# mainboard.net
KiCad netlist of a schematic drawn in EAGLE
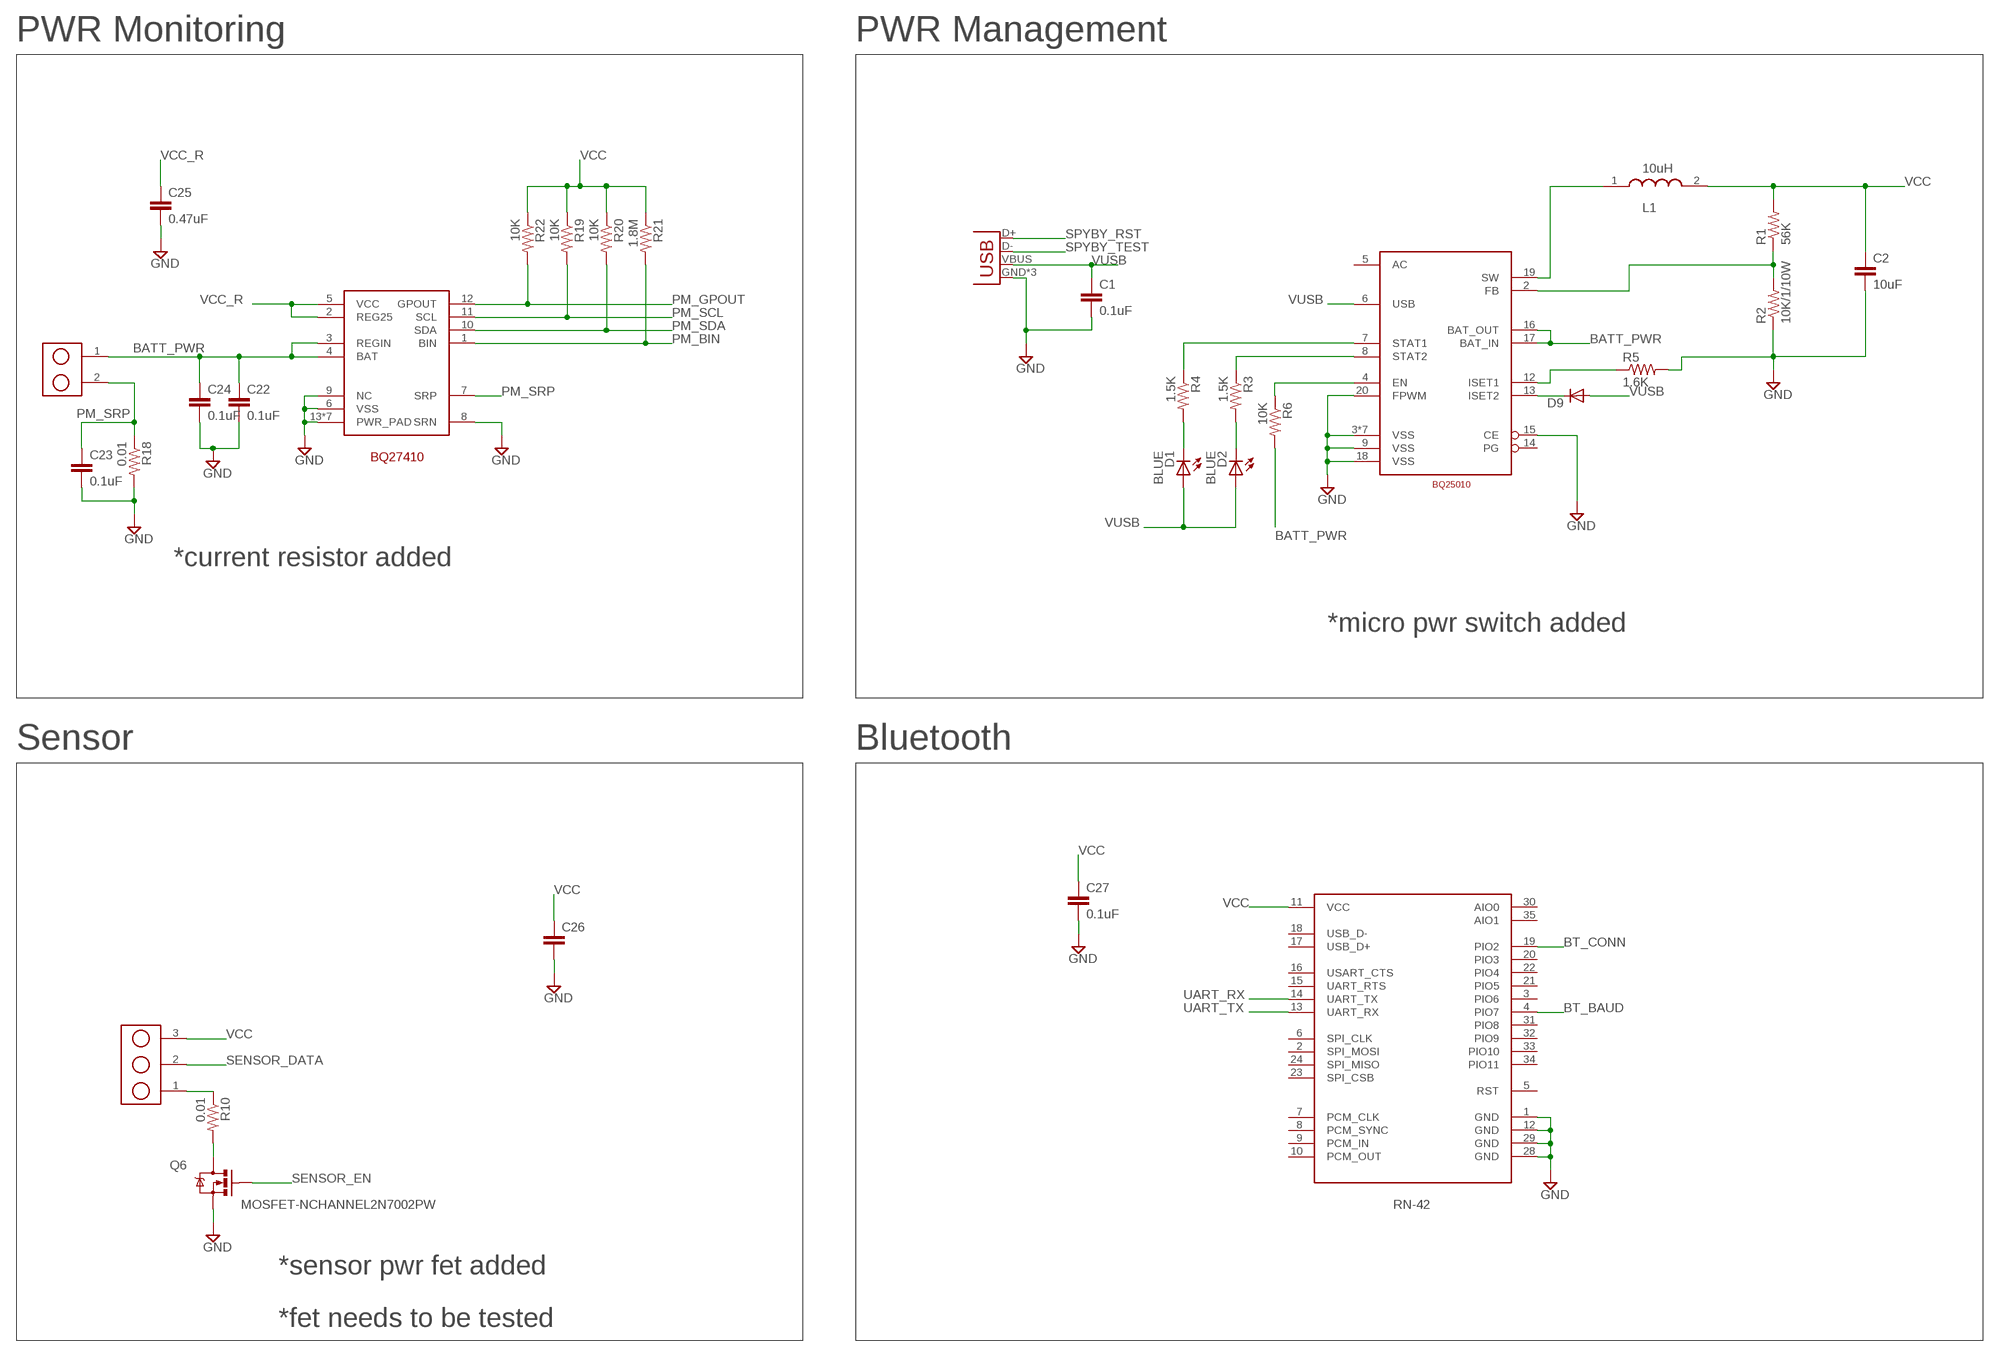
[diagram p0: schematic, sheet 1, part 1 of 2]
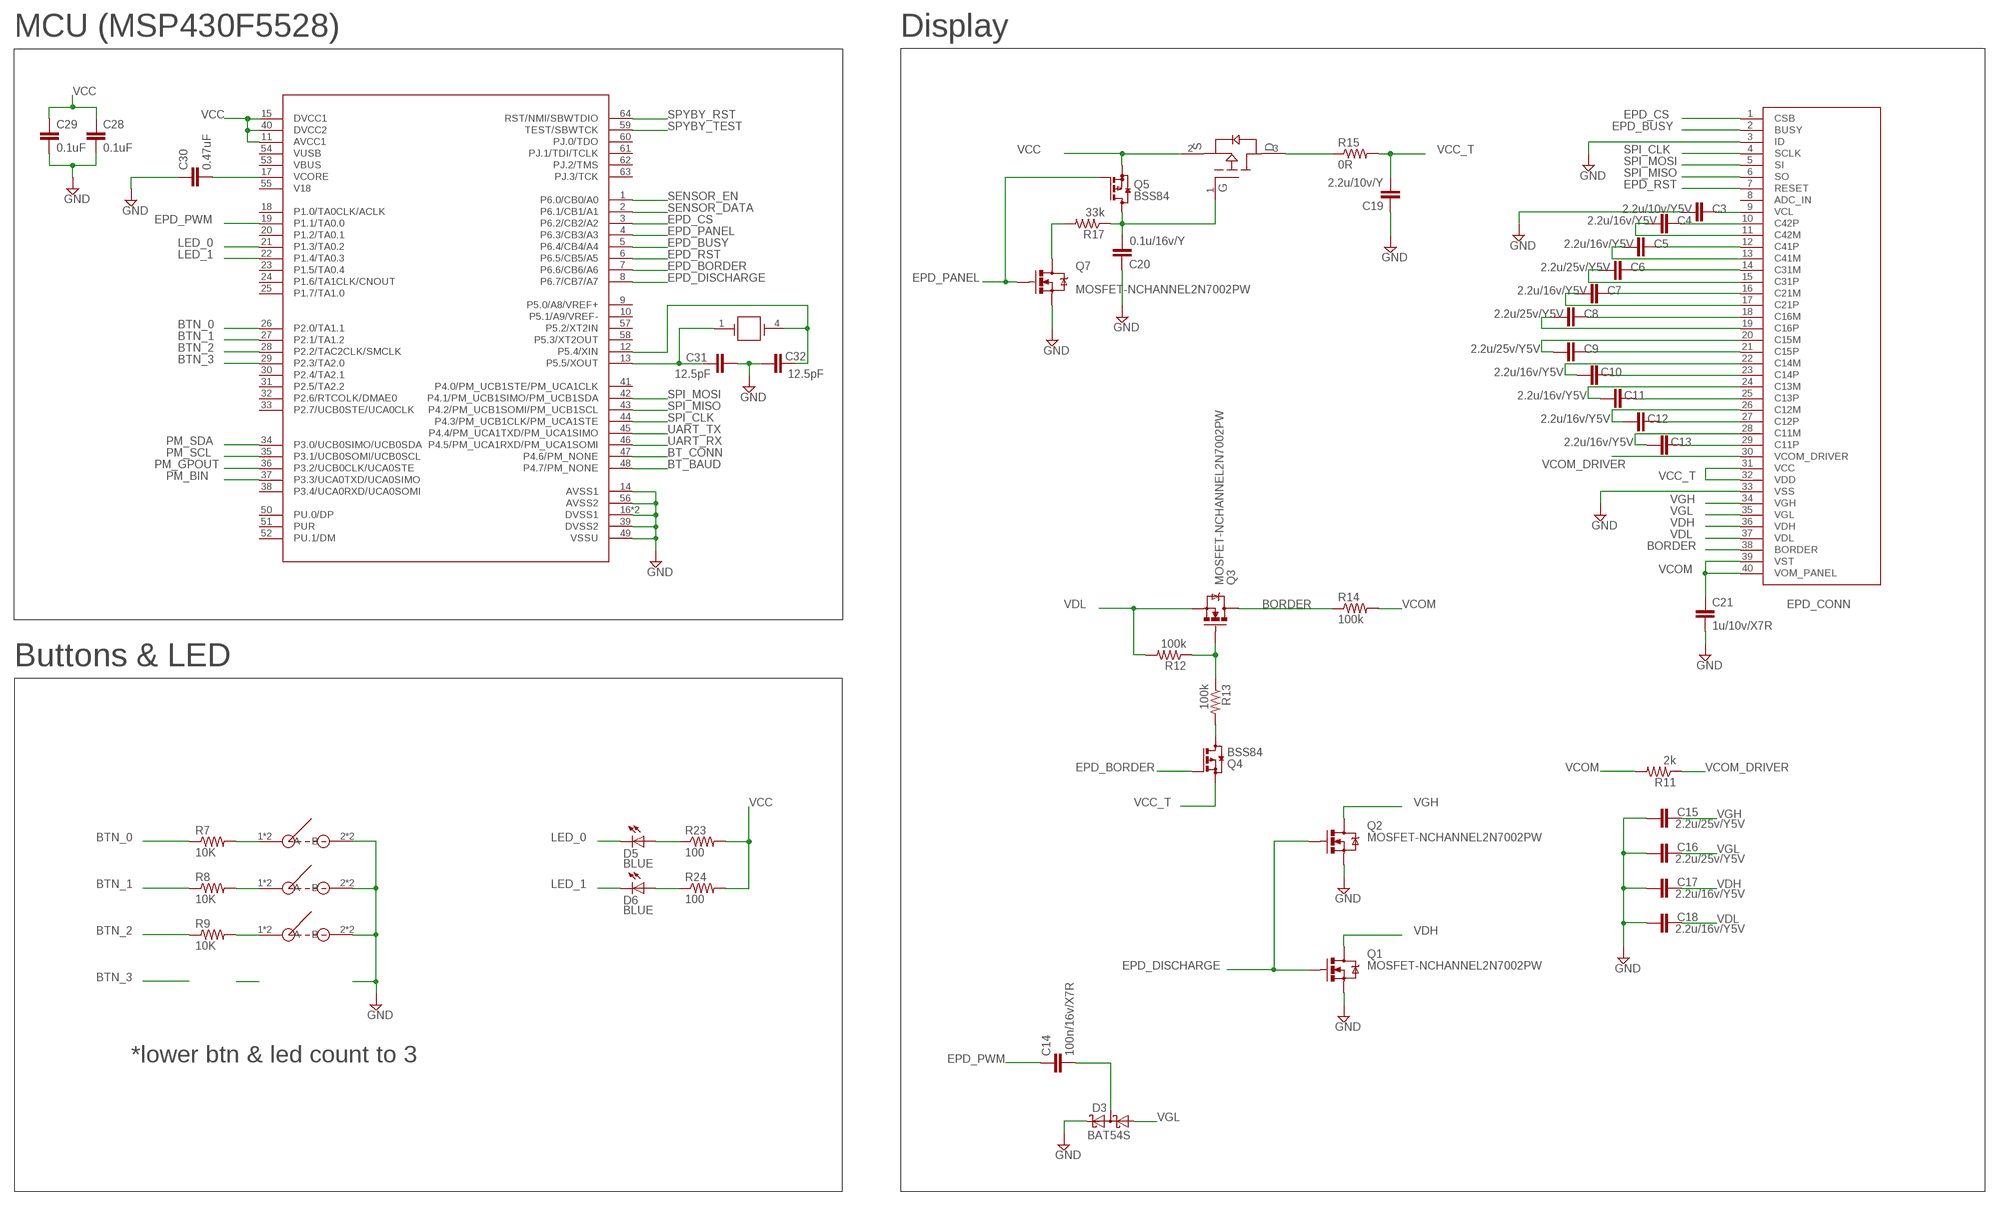
[diagram p1: schematic, sheet 1, part 2 of 2]

(export (version "E")
  (design (tool "Eeschema 10.0.6"))
  (components
    (comp (ref "AP2305")
      (value "DMG2305UX")
      (footprint "eagle-import:SOT23")
      (libsource (lib "eagle-import") (part "DMG2305UX"))
    )
    (comp (ref "C1")
      (value "0.1uF")
      (footprint "eagle-import:0402-CAP")
      (libsource (lib "eagle-import") (part "CAP0402-CAP"))
    )
    (comp (ref "C2")
      (value "10uF")
      (footprint "eagle-import:0402-CAP")
      (libsource (lib "eagle-import") (part "CAP0402-CAP"))
    )
    (comp (ref "C3")
      (value "2.2u/10v/Y5V")
      (footprint "eagle-import:0402-CAP")
      (libsource (lib "eagle-import") (part "CAP0402-CAP"))
    )
    (comp (ref "C4")
      (value "2.2u/16v/Y5V")
      (footprint "eagle-import:0402-CAP")
      (libsource (lib "eagle-import") (part "CAP0402-CAP"))
    )
    (comp (ref "C5")
      (value "2.2u/16v/Y5V")
      (footprint "eagle-import:0402-CAP")
      (libsource (lib "eagle-import") (part "CAP0402-CAP"))
    )
    (comp (ref "C6")
      (value "2.2u/25v/Y5V")
      (footprint "eagle-import:0402-CAP")
      (libsource (lib "eagle-import") (part "CAP0402-CAP"))
    )
    (comp (ref "C7")
      (value "2.2u/16v/Y5V")
      (footprint "eagle-import:0402-CAP")
      (libsource (lib "eagle-import") (part "CAP0402-CAP"))
    )
    (comp (ref "C8")
      (value "2.2u/25v/Y5V")
      (footprint "eagle-import:0402-CAP")
      (libsource (lib "eagle-import") (part "CAP0402-CAP"))
    )
    (comp (ref "C9")
      (value "2.2u/25v/Y5V")
      (footprint "eagle-import:0402-CAP")
      (libsource (lib "eagle-import") (part "CAP0402-CAP"))
    )
    (comp (ref "C10")
      (value "2.2u/16v/Y5V")
      (footprint "eagle-import:0402-CAP")
      (libsource (lib "eagle-import") (part "CAP0402-CAP"))
    )
    (comp (ref "C11")
      (value "2.2u/16v/Y5V")
      (footprint "eagle-import:0402-CAP")
      (libsource (lib "eagle-import") (part "CAP0402-CAP"))
    )
    (comp (ref "C12")
      (value "2.2u/16v/Y5V")
      (footprint "eagle-import:0402-CAP")
      (libsource (lib "eagle-import") (part "CAP0402-CAP"))
    )
    (comp (ref "C13")
      (value "2.2u/16v/Y5V")
      (footprint "eagle-import:0402-CAP")
      (libsource (lib "eagle-import") (part "CAP0402-CAP"))
    )
    (comp (ref "C14")
      (value "100n/16v/X7R")
      (footprint "eagle-import:0402-CAP")
      (libsource (lib "eagle-import") (part "CAP0402-CAP"))
    )
    (comp (ref "C15")
      (value "2.2u/25v/Y5V")
      (footprint "eagle-import:0402-CAP")
      (libsource (lib "eagle-import") (part "CAP0402-CAP"))
    )
    (comp (ref "C16")
      (value "2.2u/25v/Y5V")
      (footprint "eagle-import:0402-CAP")
      (libsource (lib "eagle-import") (part "CAP0402-CAP"))
    )
    (comp (ref "C17")
      (value "2.2u/16v/Y5V")
      (footprint "eagle-import:0402-CAP")
      (libsource (lib "eagle-import") (part "CAP0402-CAP"))
    )
    (comp (ref "C18")
      (value "2.2u/16v/Y5V")
      (footprint "eagle-import:0402-CAP")
      (libsource (lib "eagle-import") (part "CAP0402-CAP"))
    )
    (comp (ref "C19")
      (value "2.2u/10v/Y")
      (footprint "eagle-import:0402-CAP")
      (libsource (lib "eagle-import") (part "CAP0402-CAP"))
    )
    (comp (ref "C20")
      (value "0.1u/16v/Y")
      (footprint "eagle-import:0402-CAP")
      (libsource (lib "eagle-import") (part "CAP0402-CAP"))
    )
    (comp (ref "C21")
      (value "1u/10v/X7R")
      (footprint "eagle-import:0402-CAP")
      (libsource (lib "eagle-import") (part "CAP0402-CAP"))
    )
    (comp (ref "C22")
      (value "0.1uF")
      (footprint "eagle-import:0402-CAP")
      (libsource (lib "eagle-import") (part "CAP0402-CAP"))
    )
    (comp (ref "C23")
      (value "0.1uF")
      (footprint "eagle-import:0402-CAP")
      (libsource (lib "eagle-import") (part "CAP0402-CAP"))
    )
    (comp (ref "C24")
      (value "0.1uF")
      (footprint "eagle-import:0402-CAP")
      (libsource (lib "eagle-import") (part "CAP0402-CAP"))
    )
    (comp (ref "C25")
      (value "0.47uF")
      (footprint "eagle-import:0402-CAP")
      (libsource (lib "eagle-import") (part "CAP0402-CAP"))
    )
    (comp (ref "C26")
      (value "CAP0402-CAP")
      (footprint "eagle-import:0402-CAP")
      (libsource (lib "eagle-import") (part "CAP0402-CAP"))
    )
    (comp (ref "C27")
      (value "0.1uF")
      (footprint "eagle-import:0402-CAP")
      (libsource (lib "eagle-import") (part "CAP0402-CAP"))
    )
    (comp (ref "C28")
      (value "0.1uF")
      (footprint "eagle-import:0402-CAP")
      (libsource (lib "eagle-import") (part "CAP0402-CAP"))
    )
    (comp (ref "C29")
      (value "0.1uF")
      (footprint "eagle-import:0402-CAP")
      (libsource (lib "eagle-import") (part "CAP0402-CAP"))
    )
    (comp (ref "C30")
      (value "0.47uF")
      (footprint "eagle-import:0402-CAP")
      (libsource (lib "eagle-import") (part "CAP0402-CAP"))
    )
    (comp (ref "C31")
      (value "12.5pF")
      (footprint "eagle-import:0402-CAP")
      (libsource (lib "eagle-import") (part "CAP0402-CAP"))
    )
    (comp (ref "C32")
      (value "12.5pF")
      (footprint "eagle-import:0402-CAP")
      (libsource (lib "eagle-import") (part "CAP0402-CAP"))
    )
    (comp (ref "D1")
      (value "BLUE")
      (footprint "eagle-import:LED-0603")
      (libsource (lib "eagle-import") (part "LED-BLUE0603"))
    )
    (comp (ref "D2")
      (value "BLUE")
      (footprint "eagle-import:LED-0603")
      (libsource (lib "eagle-import") (part "LED-BLUE0603"))
    )
    (comp (ref "D3")
      (value "BAT54S")
      (footprint "eagle-import:SOT23")
      (libsource (lib "eagle-import") (part "BAT54S"))
    )
    (comp (ref "D5")
      (value "BLUE")
      (footprint "eagle-import:LED-0603")
      (libsource (lib "eagle-import") (part "LED-BLUE0603"))
    )
    (comp (ref "D6")
      (value "BLUE")
      (footprint "eagle-import:LED-0603")
      (libsource (lib "eagle-import") (part "LED-BLUE0603"))
    )
    (comp (ref "D9")
      (value "DIODESOD523")
      (footprint "eagle-import:SOD523")
      (libsource (lib "eagle-import") (part "DIODESOD523"))
    )
    (comp (ref "JP1")
      (value "USB-MICROB")
      (footprint "eagle-import:USB-MICROB")
      (libsource (lib "eagle-import") (part "USB-MICROB"))
    )
    (comp (ref "L1")
      (value "10uH")
      (footprint "eagle-import:ASPI_0428S-100M-T")
      (libsource (lib "eagle-import") (part "ASPI-0428S-100M-T"))
    )
    (comp (ref "Q1")
      (value "MOSFET-NCHANNEL2N7002PW")
      (footprint "eagle-import:SOT323")
      (libsource (lib "eagle-import") (part "MOSFET-NCHANNEL2N7002PW"))
    )
    (comp (ref "Q2")
      (value "MOSFET-NCHANNEL2N7002PW")
      (footprint "eagle-import:SOT323")
      (libsource (lib "eagle-import") (part "MOSFET-NCHANNEL2N7002PW"))
    )
    (comp (ref "Q3")
      (value "MOSFET-NCHANNEL2N7002PW")
      (footprint "eagle-import:SOT323")
      (libsource (lib "eagle-import") (part "MOSFET-NCHANNEL2N7002PW"))
    )
    (comp (ref "Q4")
      (value "BSS84")
      (footprint "eagle-import:SOT23")
      (libsource (lib "eagle-import") (part "BSS84"))
    )
    (comp (ref "Q5")
      (value "BSS84")
      (footprint "eagle-import:SOT23")
      (libsource (lib "eagle-import") (part "BSS84"))
    )
    (comp (ref "Q6")
      (value "MOSFET-NCHANNEL2N7002PW")
      (footprint "eagle-import:SOT323")
      (libsource (lib "eagle-import") (part "MOSFET-NCHANNEL2N7002PW"))
    )
    (comp (ref "Q7")
      (value "MOSFET-NCHANNEL2N7002PW")
      (footprint "eagle-import:SOT323")
      (libsource (lib "eagle-import") (part "MOSFET-NCHANNEL2N7002PW"))
    )
    (comp (ref "R1")
      (value "56K")
      (footprint "eagle-import:0402-RES")
      (libsource (lib "eagle-import") (part "RESISTOR0402-RES"))
    )
    (comp (ref "R2")
      (value "10K/1/10W")
      (footprint "eagle-import:0402-RES")
      (libsource (lib "eagle-import") (part "RESISTOR0402-RES"))
    )
    (comp (ref "R3")
      (value "1.5K")
      (footprint "eagle-import:0402-RES")
      (libsource (lib "eagle-import") (part "RESISTOR0402-RES"))
    )
    (comp (ref "R4")
      (value "1.5K")
      (footprint "eagle-import:0402-RES")
      (libsource (lib "eagle-import") (part "RESISTOR0402-RES"))
    )
    (comp (ref "R5")
      (value "1.6K")
      (footprint "eagle-import:0402-RES")
      (libsource (lib "eagle-import") (part "RESISTOR0402-RES"))
    )
    (comp (ref "R6")
      (value "10K")
      (footprint "eagle-import:0402-RES")
      (libsource (lib "eagle-import") (part "RESISTOR0402-RES"))
    )
    (comp (ref "R7")
      (value "10K")
      (footprint "eagle-import:0402-RES")
      (libsource (lib "eagle-import") (part "RESISTOR0402-RES"))
    )
    (comp (ref "R8")
      (value "10K")
      (footprint "eagle-import:0402-RES")
      (libsource (lib "eagle-import") (part "RESISTOR0402-RES"))
    )
    (comp (ref "R9")
      (value "10K")
      (footprint "eagle-import:0402-RES")
      (libsource (lib "eagle-import") (part "RESISTOR0402-RES"))
    )
    (comp (ref "R10")
      (value "0.01")
      (footprint "eagle-import:0402-RES")
      (libsource (lib "eagle-import") (part "RESISTOR0402-RES"))
    )
    (comp (ref "R11")
      (value "2k")
      (footprint "eagle-import:0402-RES")
      (libsource (lib "eagle-import") (part "RESISTOR0402-RES"))
    )
    (comp (ref "R12")
      (value "100k")
      (footprint "eagle-import:0402-RES")
      (libsource (lib "eagle-import") (part "RESISTOR0402-RES"))
    )
    (comp (ref "R13")
      (value "100k")
      (footprint "eagle-import:0402-RES")
      (libsource (lib "eagle-import") (part "RESISTOR0402-RES"))
    )
    (comp (ref "R14")
      (value "100k")
      (footprint "eagle-import:0402-RES")
      (libsource (lib "eagle-import") (part "RESISTOR0402-RES"))
    )
    (comp (ref "R15")
      (value "0R")
      (footprint "eagle-import:0402-RES")
      (libsource (lib "eagle-import") (part "RESISTOR0402-RES"))
    )
    (comp (ref "R17")
      (value "33k")
      (footprint "eagle-import:0402-RES")
      (libsource (lib "eagle-import") (part "RESISTOR0402-RES"))
    )
    (comp (ref "R18")
      (value "0.01")
      (footprint "eagle-import:0402-RES")
      (libsource (lib "eagle-import") (part "RESISTOR0402-RES"))
    )
    (comp (ref "R19")
      (value "10K")
      (footprint "eagle-import:0402-RES")
      (libsource (lib "eagle-import") (part "RESISTOR0402-RES"))
    )
    (comp (ref "R20")
      (value "10K")
      (footprint "eagle-import:0402-RES")
      (libsource (lib "eagle-import") (part "RESISTOR0402-RES"))
    )
    (comp (ref "R21")
      (value "1.8M")
      (footprint "eagle-import:0402-RES")
      (libsource (lib "eagle-import") (part "RESISTOR0402-RES"))
    )
    (comp (ref "R22")
      (value "10K")
      (footprint "eagle-import:0402-RES")
      (libsource (lib "eagle-import") (part "RESISTOR0402-RES"))
    )
    (comp (ref "R23")
      (value "100")
      (footprint "eagle-import:0402-RES")
      (libsource (lib "eagle-import") (part "RESISTOR0402-RES"))
    )
    (comp (ref "R24")
      (value "100")
      (footprint "eagle-import:0402-RES")
      (libsource (lib "eagle-import") (part "RESISTOR0402-RES"))
    )
    (comp (ref "U$1")
      (value "MSP430F5528")
      (footprint "eagle-import:VQFN_RGC_64PIN")
      (libsource (lib "eagle-import") (part "MSP430F5528"))
    )
    (comp (ref "U$2")
      (value "RN-42")
      (footprint "eagle-import:RN-42")
      (libsource (lib "eagle-import") (part "RN-42"))
    )
    (comp (ref "U$3")
      (value "BQ25010")
      (footprint "eagle-import:VQFN_RHL_20PIN")
      (libsource (lib "eagle-import") (part "BQ25010"))
    )
    (comp (ref "U$4")
      (value "RA_TAC_BUTTON\"EVQPUK\"")
      (footprint "eagle-import:EVQ-PUK02K")
      (fields (field (name "PART#") "EVQ-PUK02K"))
      (libsource (lib "eagle-import") (part "RA_TAC_BUTTON{dblquote}EVQPUK{dblquote}"))
    )
    (comp (ref "U$5")
      (value "RA_TAC_BUTTON\"EVQPUK\"")
      (footprint "eagle-import:EVQ-PUK02K")
      (fields (field (name "PART#") "EVQ-PUK02K"))
      (libsource (lib "eagle-import") (part "RA_TAC_BUTTON{dblquote}EVQPUK{dblquote}"))
    )
    (comp (ref "U$6")
      (value "RA_TAC_BUTTON\"EVQPUK\"")
      (footprint "eagle-import:EVQ-PUK02K")
      (fields (field (name "PART#") "EVQ-PUK02K"))
      (libsource (lib "eagle-import") (part "RA_TAC_BUTTON{dblquote}EVQPUK{dblquote}"))
    )
    (comp (ref "U$8")
      (value "FH12-40S-0.5SH")
      (footprint "eagle-import:FH12-40S-0.5SH")
      (libsource (lib "eagle-import") (part "FH12-40S-0.5SH"))
    )
    (comp (ref "U$9")
      (value "BQ27410")
      (footprint "eagle-import:SON_DRZ_12PIN")
      (libsource (lib "eagle-import") (part "BQ27410"))
    )
    (comp (ref "U$11")
      (value "HEADER_2PIN_50MIL")
      (footprint "eagle-import:HEADER_2PIN_50MIL")
      (libsource (lib "eagle-import") (part "HEADER_2PIN_50MIL"))
    )
    (comp (ref "U$12")
      (value "HEADER_3PIN_50MIL")
      (footprint "eagle-import:HEADER_3PIN_50MIL")
      (libsource (lib "eagle-import") (part "HEADER_3PIN_50MIL"))
    )
    (comp (ref "X1")
      (value "CRYSTAL\"32.768\"")
      (footprint "eagle-import:ECS-327-12.5-17X-C-TR")
      (libsource (lib "eagle-import") (part "CRYSTAL{dblquote}32.768{dblquote}"))
    )
  )
  (nets
    (net (code "1") (name "/BATT_PWR") (class "Default")
      (node (ref "C22") (pin "1") (pinfunction "1_1") (pintype "passive"))
      (node (ref "C24") (pin "1") (pinfunction "1_1") (pintype "passive"))
      (node (ref "R6") (pin "2") (pinfunction "2_2") (pintype "passive"))
      (node (ref "U$11") (pin "1") (pinfunction "1_1") (pintype "bidirectional"))
      (node (ref "U$3") (pin "16") (pinfunction "BAT_OUT_16") (pintype "bidirectional"))
      (node (ref "U$3") (pin "17") (pinfunction "BAT_IN_17") (pintype "bidirectional"))
      (node (ref "U$9") (pin "3") (pinfunction "REGIN_3") (pintype "bidirectional"))
      (node (ref "U$9") (pin "4") (pinfunction "BAT_4") (pintype "bidirectional"))
    )
    (net (code "2") (name "/BORDER") (class "Default")
      (node (ref "Q3") (pin "3") (pinfunction "D_3") (pintype "passive"))
      (node (ref "R14") (pin "1") (pinfunction "1_1") (pintype "passive"))
      (node (ref "U$8") (pin "38") (pinfunction "BORDER_38") (pintype "bidirectional"))
    )
    (net (code "3") (name "/BTN_0") (class "Default")
      (node (ref "R7") (pin "1") (pinfunction "1_1") (pintype "passive"))
      (node (ref "U$1") (pin "26") (pinfunction "P2.0/TA1.1_26") (pintype "bidirectional"))
    )
    (net (code "4") (name "/BTN_1") (class "Default")
      (node (ref "R8") (pin "1") (pinfunction "1_1") (pintype "passive"))
      (node (ref "U$1") (pin "27") (pinfunction "P2.1/TA1.2_27") (pintype "bidirectional"))
    )
    (net (code "5") (name "/BTN_2") (class "Default")
      (node (ref "R9") (pin "1") (pinfunction "1_1") (pintype "passive"))
      (node (ref "U$1") (pin "28") (pinfunction "P2.2/TAC2CLK/SMCLK_28") (pintype "bidirectional"))
    )
    (net (code "6") (name "/BTN_3") (class "Default")
      (node (ref "U$1") (pin "29") (pinfunction "P2.3/TA2.0_29") (pintype "bidirectional"))
    )
    (net (code "7") (name "/BT_BAUD") (class "Default")
      (node (ref "U$1") (pin "48") (pinfunction "P4.7/PM_NONE_48") (pintype "bidirectional"))
      (node (ref "U$2") (pin "4") (pinfunction "PIO7_4") (pintype "bidirectional"))
    )
    (net (code "8") (name "/BT_CONN") (class "Default")
      (node (ref "U$1") (pin "47") (pinfunction "P4.6/PM_NONE_47") (pintype "bidirectional"))
      (node (ref "U$2") (pin "19") (pinfunction "PIO2_19") (pintype "bidirectional"))
    )
    (net (code "9") (name "/EPD_BORDER") (class "Default")
      (node (ref "Q4") (pin "1") (pinfunction "G_1") (pintype "passive"))
      (node (ref "U$1") (pin "7") (pinfunction "P6.6/CB6/A6_7") (pintype "bidirectional"))
    )
    (net (code "10") (name "/EPD_BUSY") (class "Default")
      (node (ref "U$1") (pin "5") (pinfunction "P6.4/CB4/A4_5") (pintype "bidirectional"))
      (node (ref "U$8") (pin "2") (pinfunction "BUSY_2") (pintype "bidirectional"))
    )
    (net (code "11") (name "/EPD_CS") (class "Default")
      (node (ref "U$1") (pin "3") (pinfunction "P6.2/CB2/A2_3") (pintype "bidirectional"))
      (node (ref "U$8") (pin "1") (pinfunction "CSB_1") (pintype "bidirectional"))
    )
    (net (code "12") (name "/EPD_DISCHARGE") (class "Default")
      (node (ref "Q1") (pin "1") (pinfunction "G_1") (pintype "passive"))
      (node (ref "Q2") (pin "1") (pinfunction "G_1") (pintype "passive"))
      (node (ref "U$1") (pin "8") (pinfunction "P6.7/CB7/A7_8") (pintype "bidirectional"))
    )
    (net (code "13") (name "/EPD_PANEL") (class "Default")
      (node (ref "Q5") (pin "1") (pinfunction "G_1") (pintype "passive"))
      (node (ref "Q7") (pin "1") (pinfunction "G_1") (pintype "passive"))
      (node (ref "U$1") (pin "4") (pinfunction "P6.3/CB3/A3_4") (pintype "bidirectional"))
    )
    (net (code "14") (name "/EPD_PWM") (class "Default")
      (node (ref "C14") (pin "1") (pinfunction "1_1") (pintype "passive"))
      (node (ref "U$1") (pin "19") (pinfunction "P1.1/TA0.0_19") (pintype "bidirectional"))
    )
    (net (code "15") (name "/EPD_RST") (class "Default")
      (node (ref "U$1") (pin "6") (pinfunction "P6.5/CB5/A5_6") (pintype "bidirectional"))
      (node (ref "U$8") (pin "7") (pinfunction "RESET_7") (pintype "bidirectional"))
    )
    (net (code "16") (name "/LED_0") (class "Default")
      (node (ref "D5") (pin "C") (pinfunction "C_C") (pintype "passive"))
      (node (ref "U$1") (pin "21") (pinfunction "P1.3/TA0.2_21") (pintype "bidirectional"))
    )
    (net (code "17") (name "/LED_1") (class "Default")
      (node (ref "D6") (pin "C") (pinfunction "C_C") (pintype "passive"))
      (node (ref "U$1") (pin "22") (pinfunction "P1.4/TA0.3_22") (pintype "bidirectional"))
    )
    (net (code "18") (name "/PM_BIN") (class "Default")
      (node (ref "R21") (pin "2") (pinfunction "2_2") (pintype "passive"))
      (node (ref "U$1") (pin "37") (pinfunction "P3.3/UCA0TXD/UCA0SIMO_37") (pintype "bidirectional"))
      (node (ref "U$9") (pin "1") (pinfunction "BIN_1") (pintype "bidirectional"))
    )
    (net (code "19") (name "/PM_GPOUT") (class "Default")
      (node (ref "R22") (pin "2") (pinfunction "2_2") (pintype "passive"))
      (node (ref "U$1") (pin "36") (pinfunction "P3.2/UCB0CLK/UCA0STE_36") (pintype "bidirectional"))
      (node (ref "U$9") (pin "12") (pinfunction "GPOUT_12") (pintype "bidirectional"))
    )
    (net (code "20") (name "/PM_SCL") (class "Default")
      (node (ref "R19") (pin "2") (pinfunction "2_2") (pintype "passive"))
      (node (ref "U$1") (pin "35") (pinfunction "P3.1/UCB0SOMI/UCB0SCL_35") (pintype "bidirectional"))
      (node (ref "U$9") (pin "11") (pinfunction "SCL_11") (pintype "bidirectional"))
    )
    (net (code "21") (name "/PM_SDA") (class "Default")
      (node (ref "R20") (pin "2") (pinfunction "2_2") (pintype "passive"))
      (node (ref "U$1") (pin "34") (pinfunction "P3.0/UCB0SIMO/UCB0SDA_34") (pintype "bidirectional"))
      (node (ref "U$9") (pin "10") (pinfunction "SDA_10") (pintype "bidirectional"))
    )
    (net (code "22") (name "/PM_SRP") (class "Default")
      (node (ref "C23") (pin "1") (pinfunction "1_1") (pintype "passive"))
      (node (ref "R18") (pin "1") (pinfunction "1_1") (pintype "passive"))
      (node (ref "U$11") (pin "2") (pinfunction "2_2") (pintype "bidirectional"))
      (node (ref "U$9") (pin "7") (pinfunction "SRP_7") (pintype "bidirectional"))
    )
    (net (code "23") (name "/SENSOR_DATA") (class "Default")
      (node (ref "U$1") (pin "2") (pinfunction "P6.1/CB1/A1_2") (pintype "bidirectional"))
      (node (ref "U$12") (pin "2") (pinfunction "P$2_2") (pintype "bidirectional"))
    )
    (net (code "24") (name "/SENSOR_EN") (class "Default")
      (node (ref "Q6") (pin "1") (pinfunction "G_1") (pintype "passive"))
      (node (ref "U$1") (pin "1") (pinfunction "P6.0/CB0/A0_1") (pintype "bidirectional"))
    )
    (net (code "25") (name "/SPI_CLK") (class "Default")
      (node (ref "U$1") (pin "44") (pinfunction "P4.3/PM_UCB1CLK/PM_UCA1STE_44") (pintype "bidirectional"))
      (node (ref "U$8") (pin "4") (pinfunction "SCLK_4") (pintype "bidirectional"))
    )
    (net (code "26") (name "/SPI_MISO") (class "Default")
      (node (ref "U$1") (pin "43") (pinfunction "P4.2/PM_UCB1SOMI/PM_UCB1SCL_43") (pintype "bidirectional"))
      (node (ref "U$8") (pin "6") (pinfunction "SO_6") (pintype "bidirectional"))
    )
    (net (code "27") (name "/SPI_MOSI") (class "Default")
      (node (ref "U$1") (pin "42") (pinfunction "P4.1/PM_UCB1SIMO/PM_UCB1SDA_42") (pintype "bidirectional"))
      (node (ref "U$8") (pin "5") (pinfunction "SI_5") (pintype "bidirectional"))
    )
    (net (code "28") (name "/SPYBY_RST") (class "Default")
      (node (ref "JP1") (pin "D+") (pinfunction "D+_D+") (pintype "bidirectional"))
      (node (ref "U$1") (pin "64") (pinfunction "RST/NMI/SBWTDIO_64") (pintype "bidirectional"))
    )
    (net (code "29") (name "/SPYBY_TEST") (class "Default")
      (node (ref "JP1") (pin "D-") (pinfunction "D-_D-") (pintype "bidirectional"))
      (node (ref "U$1") (pin "59") (pinfunction "TEST/SBWTCK_59") (pintype "bidirectional"))
    )
    (net (code "30") (name "/UART_RX") (class "Default")
      (node (ref "U$1") (pin "46") (pinfunction "P4.5/PM_UCA1RXD/PM_UCA1SOMI_46") (pintype "bidirectional"))
      (node (ref "U$2") (pin "14") (pinfunction "UART_TX_14") (pintype "bidirectional"))
    )
    (net (code "31") (name "/UART_TX") (class "Default")
      (node (ref "U$1") (pin "45") (pinfunction "P4.4/PM_UCA1TXD/PM_UCA1SIMO_45") (pintype "bidirectional"))
      (node (ref "U$2") (pin "13") (pinfunction "UART_RX_13") (pintype "bidirectional"))
    )
    (net (code "32") (name "/VCC") (class "Default")
      (node (ref "AP2305") (pin "2") (pinfunction "SOURCE_2") (pintype "bidirectional"))
      (node (ref "C2") (pin "1") (pinfunction "1_1") (pintype "passive"))
      (node (ref "C26") (pin "1") (pinfunction "1_1") (pintype "passive"))
      (node (ref "C27") (pin "1") (pinfunction "1_1") (pintype "passive"))
      (node (ref "C28") (pin "1") (pinfunction "1_1") (pintype "passive"))
      (node (ref "C29") (pin "1") (pinfunction "1_1") (pintype "passive"))
      (node (ref "L1") (pin "2") (pinfunction "P$2_2") (pintype "bidirectional"))
      (node (ref "Q5") (pin "2") (pinfunction "S_2") (pintype "passive"))
      (node (ref "R1") (pin "2") (pinfunction "2_2") (pintype "passive"))
      (node (ref "R19") (pin "1") (pinfunction "1_1") (pintype "passive"))
      (node (ref "R20") (pin "1") (pinfunction "1_1") (pintype "passive"))
      (node (ref "R21") (pin "1") (pinfunction "1_1") (pintype "passive"))
      (node (ref "R22") (pin "1") (pinfunction "1_1") (pintype "passive"))
      (node (ref "R23") (pin "2") (pinfunction "2_2") (pintype "passive"))
      (node (ref "R24") (pin "2") (pinfunction "2_2") (pintype "passive"))
      (node (ref "U$1") (pin "11") (pinfunction "AVCC1_11") (pintype "bidirectional"))
      (node (ref "U$1") (pin "15") (pinfunction "DVCC1_15") (pintype "bidirectional"))
      (node (ref "U$1") (pin "40") (pinfunction "DVCC2_40") (pintype "bidirectional"))
      (node (ref "U$12") (pin "3") (pinfunction "P$3_3") (pintype "bidirectional"))
      (node (ref "U$2") (pin "11") (pinfunction "VCC_11") (pintype "bidirectional"))
    )
    (net (code "33") (name "/VCC_R") (class "Default")
      (node (ref "C25") (pin "1") (pinfunction "1_1") (pintype "passive"))
      (node (ref "U$9") (pin "2") (pinfunction "REG25_2") (pintype "bidirectional"))
      (node (ref "U$9") (pin "5") (pinfunction "VCC_5") (pintype "bidirectional"))
    )
    (net (code "34") (name "/VCC_T") (class "Default")
      (node (ref "C19") (pin "2") (pinfunction "2_2") (pintype "passive"))
      (node (ref "Q4") (pin "2") (pinfunction "S_2") (pintype "passive"))
      (node (ref "R15") (pin "2") (pinfunction "2_2") (pintype "passive"))
      (node (ref "U$8") (pin "31") (pinfunction "VCC_31") (pintype "bidirectional"))
      (node (ref "U$8") (pin "32") (pinfunction "VDD_32") (pintype "bidirectional"))
    )
    (net (code "35") (name "/VCOM") (class "Default")
      (node (ref "C21") (pin "1") (pinfunction "1_1") (pintype "passive"))
      (node (ref "R11") (pin "2") (pinfunction "2_2") (pintype "passive"))
      (node (ref "R14") (pin "2") (pinfunction "2_2") (pintype "passive"))
      (node (ref "U$8") (pin "39") (pinfunction "VST_39") (pintype "bidirectional"))
      (node (ref "U$8") (pin "40") (pinfunction "VOM_PANEL_40") (pintype "bidirectional"))
    )
    (net (code "36") (name "/VCOM_DRIVER") (class "Default")
      (node (ref "R11") (pin "1") (pinfunction "1_1") (pintype "passive"))
      (node (ref "U$8") (pin "30") (pinfunction "VCOM_DRIVER_30") (pintype "bidirectional"))
    )
    (net (code "37") (name "/VDH") (class "Default")
      (node (ref "C17") (pin "2") (pinfunction "2_2") (pintype "passive"))
      (node (ref "Q1") (pin "3") (pinfunction "D_3") (pintype "passive"))
      (node (ref "U$8") (pin "36") (pinfunction "VDH_36") (pintype "bidirectional"))
    )
    (net (code "38") (name "/VDL") (class "Default")
      (node (ref "C18") (pin "2") (pinfunction "2_2") (pintype "passive"))
      (node (ref "Q3") (pin "2") (pinfunction "S_2") (pintype "passive"))
      (node (ref "R12") (pin "2") (pinfunction "2_2") (pintype "passive"))
      (node (ref "U$8") (pin "37") (pinfunction "VDL_37") (pintype "bidirectional"))
    )
    (net (code "39") (name "/VGH") (class "Default")
      (node (ref "C15") (pin "2") (pinfunction "2_2") (pintype "passive"))
      (node (ref "Q2") (pin "3") (pinfunction "D_3") (pintype "passive"))
      (node (ref "U$8") (pin "34") (pinfunction "VGH_34") (pintype "bidirectional"))
    )
    (net (code "40") (name "/VGL") (class "Default")
      (node (ref "C16") (pin "2") (pinfunction "2_2") (pintype "passive"))
      (node (ref "D3") (pin "1") (pinfunction "A1_1") (pintype "passive"))
      (node (ref "U$8") (pin "35") (pinfunction "VGL_35") (pintype "bidirectional"))
    )
    (net (code "41") (name "/VUSB") (class "Default")
      (node (ref "C1") (pin "1") (pinfunction "1_1") (pintype "passive"))
      (node (ref "D1") (pin "A") (pinfunction "A_A") (pintype "passive"))
      (node (ref "D2") (pin "A") (pinfunction "A_A") (pintype "passive"))
      (node (ref "D9") (pin "A") (pinfunction "A_A") (pintype "passive"))
      (node (ref "JP1") (pin "VBUS") (pinfunction "VBUS_VBUS") (pintype "bidirectional"))
      (node (ref "U$3") (pin "6") (pinfunction "USB_6") (pintype "bidirectional"))
    )
    (net (code "42") (name "GND") (class "Default")
      (node (ref "C1") (pin "2") (pinfunction "2_2") (pintype "passive"))
      (node (ref "C15") (pin "1") (pinfunction "1_1") (pintype "passive"))
      (node (ref "C16") (pin "1") (pinfunction "1_1") (pintype "passive"))
      (node (ref "C17") (pin "1") (pinfunction "1_1") (pintype "passive"))
      (node (ref "C18") (pin "1") (pinfunction "1_1") (pintype "passive"))
      (node (ref "C19") (pin "1") (pinfunction "1_1") (pintype "passive"))
      (node (ref "C2") (pin "2") (pinfunction "2_2") (pintype "passive"))
      (node (ref "C20") (pin "1") (pinfunction "1_1") (pintype "passive"))
      (node (ref "C21") (pin "2") (pinfunction "2_2") (pintype "passive"))
      (node (ref "C22") (pin "2") (pinfunction "2_2") (pintype "passive"))
      (node (ref "C23") (pin "2") (pinfunction "2_2") (pintype "passive"))
      (node (ref "C24") (pin "2") (pinfunction "2_2") (pintype "passive"))
      (node (ref "C25") (pin "2") (pinfunction "2_2") (pintype "passive"))
      (node (ref "C26") (pin "2") (pinfunction "2_2") (pintype "passive"))
      (node (ref "C27") (pin "2") (pinfunction "2_2") (pintype "passive"))
      (node (ref "C28") (pin "2") (pinfunction "2_2") (pintype "passive"))
      (node (ref "C29") (pin "2") (pinfunction "2_2") (pintype "passive"))
      (node (ref "C3") (pin "1") (pinfunction "1_1") (pintype "passive"))
      (node (ref "C30") (pin "1") (pinfunction "1_1") (pintype "passive"))
      (node (ref "C31") (pin "2") (pinfunction "2_2") (pintype "passive"))
      (node (ref "C32") (pin "1") (pinfunction "1_1") (pintype "passive"))
      (node (ref "D3") (pin "2") (pinfunction "C2_2") (pintype "passive"))
      (node (ref "JP1") (pin "GND") (pinfunction "GND_GND") (pintype "bidirectional"))
      (node (ref "JP1") (pin "MT1") (pinfunction "GND_MT1") (pintype "bidirectional"))
      (node (ref "JP1") (pin "MT2") (pinfunction "GND_MT2") (pintype "bidirectional"))
      (node (ref "Q1") (pin "2") (pinfunction "S_2") (pintype "passive"))
      (node (ref "Q2") (pin "2") (pinfunction "S_2") (pintype "passive"))
      (node (ref "Q6") (pin "2") (pinfunction "S_2") (pintype "passive"))
      (node (ref "Q7") (pin "2") (pinfunction "S_2") (pintype "passive"))
      (node (ref "R18") (pin "2") (pinfunction "2_2") (pintype "passive"))
      (node (ref "R2") (pin "1") (pinfunction "1_1") (pintype "passive"))
      (node (ref "R5") (pin "2") (pinfunction "2_2") (pintype "passive"))
      (node (ref "U$1") (pin "14") (pinfunction "AVSS1_14") (pintype "bidirectional"))
      (node (ref "U$1") (pin "16") (pinfunction "DVSS1_16") (pintype "bidirectional"))
      (node (ref "U$1") (pin "39") (pinfunction "DVSS2_39") (pintype "bidirectional"))
      (node (ref "U$1") (pin "49") (pinfunction "VSSU_49") (pintype "bidirectional"))
      (node (ref "U$1") (pin "56") (pinfunction "AVSS2_56") (pintype "bidirectional"))
      (node (ref "U$1") (pin "P$1") (pinfunction "DVSS1_P$1") (pintype "bidirectional"))
      (node (ref "U$2") (pin "1") (pinfunction "GND_1") (pintype "bidirectional"))
      (node (ref "U$2") (pin "12") (pinfunction "GND_12") (pintype "bidirectional"))
      (node (ref "U$2") (pin "28") (pinfunction "GND_28") (pintype "bidirectional"))
      (node (ref "U$2") (pin "29") (pinfunction "GND_29") (pintype "bidirectional"))
      (node (ref "U$3") (pin "15") (pinfunction "CE_15") (pintype "bidirectional"))
      (node (ref "U$3") (pin "18") (pinfunction "VSS_18") (pintype "bidirectional"))
      (node (ref "U$3") (pin "20") (pinfunction "FPWM_20") (pintype "bidirectional"))
      (node (ref "U$3") (pin "3") (pinfunction "VSS_3") (pintype "bidirectional"))
      (node (ref "U$3") (pin "9") (pinfunction "VSS_9") (pintype "bidirectional"))
      (node (ref "U$3") (pin "P$21") (pinfunction "VSS_P$21") (pintype "bidirectional"))
      (node (ref "U$3") (pin "P$22") (pinfunction "VSS_P$22") (pintype "bidirectional"))
      (node (ref "U$3") (pin "P$23") (pinfunction "VSS_P$23") (pintype "bidirectional"))
      (node (ref "U$3") (pin "P$24") (pinfunction "VSS_P$24") (pintype "bidirectional"))
      (node (ref "U$3") (pin "P$25") (pinfunction "VSS_P$25") (pintype "bidirectional"))
      (node (ref "U$3") (pin "P$26") (pinfunction "VSS_P$26") (pintype "bidirectional"))
      (node (ref "U$4") (pin "2") (pinfunction "B_2") (pintype "bidirectional"))
      (node (ref "U$4") (pin "4") (pinfunction "B_4") (pintype "bidirectional"))
      (node (ref "U$5") (pin "2") (pinfunction "B_2") (pintype "bidirectional"))
      (node (ref "U$5") (pin "4") (pinfunction "B_4") (pintype "bidirectional"))
      (node (ref "U$6") (pin "2") (pinfunction "B_2") (pintype "bidirectional"))
      (node (ref "U$6") (pin "4") (pinfunction "B_4") (pintype "bidirectional"))
      (node (ref "U$8") (pin "3") (pinfunction "ID_3") (pintype "bidirectional"))
      (node (ref "U$8") (pin "33") (pinfunction "VSS_33") (pintype "bidirectional"))
      (node (ref "U$9") (pin "13") (pinfunction "PWR_PAD_13") (pintype "bidirectional"))
      (node (ref "U$9") (pin "6") (pinfunction "VSS_6") (pintype "bidirectional"))
      (node (ref "U$9") (pin "8") (pinfunction "SRN_8") (pintype "bidirectional"))
      (node (ref "U$9") (pin "9") (pinfunction "NC_9") (pintype "bidirectional"))
      (node (ref "U$9") (pin "P$15") (pinfunction "PWR_PAD_P$15") (pintype "bidirectional"))
      (node (ref "U$9") (pin "P$16") (pinfunction "PWR_PAD_P$16") (pintype "bidirectional"))
      (node (ref "U$9") (pin "P$17") (pinfunction "PWR_PAD_P$17") (pintype "bidirectional"))
      (node (ref "U$9") (pin "P$18") (pinfunction "PWR_PAD_P$18") (pintype "bidirectional"))
      (node (ref "U$9") (pin "P$19") (pinfunction "PWR_PAD_P$19") (pintype "bidirectional"))
      (node (ref "U$9") (pin "P$20") (pinfunction "PWR_PAD_P$20") (pintype "bidirectional"))
    )
    (net (code "43") (name "Net-(AP2305-DRAIN)") (class "Default")
      (node (ref "AP2305") (pin "3") (pinfunction "DRAIN_3") (pintype "bidirectional"))
      (node (ref "R15") (pin "1") (pinfunction "1_1") (pintype "passive"))
    )
    (net (code "44") (name "Net-(AP2305-GATE)") (class "Default")
      (node (ref "AP2305") (pin "1") (pinfunction "GATE_1") (pintype "bidirectional"))
      (node (ref "C20") (pin "2") (pinfunction "2_2") (pintype "passive"))
      (node (ref "Q5") (pin "3") (pinfunction "D_3") (pintype "passive"))
      (node (ref "R17") (pin "1") (pinfunction "1_1") (pintype "passive"))
    )
    (net (code "45") (name "Net-(D1-PadC)") (class "Default")
      (node (ref "D1") (pin "C") (pinfunction "C_C") (pintype "passive"))
      (node (ref "R4") (pin "2") (pinfunction "2_2") (pintype "passive"))
    )
    (net (code "46") (name "Net-(D2-PadC)") (class "Default")
      (node (ref "D2") (pin "C") (pinfunction "C_C") (pintype "passive"))
      (node (ref "R3") (pin "2") (pinfunction "2_2") (pintype "passive"))
    )
    (net (code "47") (name "Net-(D3-C1A2)") (class "Default")
      (node (ref "C14") (pin "2") (pinfunction "2_2") (pintype "passive"))
      (node (ref "D3") (pin "3") (pinfunction "C1A2_3") (pintype "passive"))
    )
    (net (code "48") (name "Net-(D5-PadA)") (class "Default")
      (node (ref "D5") (pin "A") (pinfunction "A_A") (pintype "passive"))
      (node (ref "R23") (pin "1") (pinfunction "1_1") (pintype "passive"))
    )
    (net (code "49") (name "Net-(D6-PadA)") (class "Default")
      (node (ref "D6") (pin "A") (pinfunction "A_A") (pintype "passive"))
      (node (ref "R24") (pin "1") (pinfunction "1_1") (pintype "passive"))
    )
    (net (code "50") (name "Net-(L1-P$1)") (class "Default")
      (node (ref "L1") (pin "1") (pinfunction "P$1_1") (pintype "bidirectional"))
      (node (ref "U$3") (pin "19") (pinfunction "SW_19") (pintype "bidirectional"))
    )
    (net (code "51") (name "Net-(Q3-G)") (class "Default")
      (node (ref "Q3") (pin "1") (pinfunction "G_1") (pintype "passive"))
      (node (ref "R12") (pin "1") (pinfunction "1_1") (pintype "passive"))
      (node (ref "R13") (pin "1") (pinfunction "1_1") (pintype "passive"))
    )
    (net (code "52") (name "Net-(Q4-D)") (class "Default")
      (node (ref "Q4") (pin "3") (pinfunction "D_3") (pintype "passive"))
      (node (ref "R13") (pin "2") (pinfunction "2_2") (pintype "passive"))
    )
    (net (code "53") (name "Net-(Q6-D)") (class "Default")
      (node (ref "Q6") (pin "3") (pinfunction "D_3") (pintype "passive"))
      (node (ref "R10") (pin "2") (pinfunction "2_2") (pintype "passive"))
    )
    (net (code "54") (name "Net-(Q7-D)") (class "Default")
      (node (ref "Q7") (pin "3") (pinfunction "D_3") (pintype "passive"))
      (node (ref "R17") (pin "2") (pinfunction "2_2") (pintype "passive"))
    )
    (net (code "55") (name "Net-(R7-Pad2)") (class "Default")
      (node (ref "R7") (pin "2") (pinfunction "2_2") (pintype "passive"))
      (node (ref "U$4") (pin "1") (pinfunction "A_1") (pintype "bidirectional"))
      (node (ref "U$4") (pin "3") (pinfunction "A_3") (pintype "bidirectional"))
    )
    (net (code "56") (name "Net-(R8-Pad2)") (class "Default")
      (node (ref "R8") (pin "2") (pinfunction "2_2") (pintype "passive"))
      (node (ref "U$5") (pin "1") (pinfunction "A_1") (pintype "bidirectional"))
      (node (ref "U$5") (pin "3") (pinfunction "A_3") (pintype "bidirectional"))
    )
    (net (code "57") (name "Net-(R9-Pad2)") (class "Default")
      (node (ref "R9") (pin "2") (pinfunction "2_2") (pintype "passive"))
      (node (ref "U$6") (pin "1") (pinfunction "A_1") (pintype "bidirectional"))
      (node (ref "U$6") (pin "3") (pinfunction "A_3") (pintype "bidirectional"))
    )
    (net (code "58") (name "Net-(U$1-P5.4{slash}XIN)") (class "Default")
      (node (ref "C32") (pin "2") (pinfunction "2_2") (pintype "passive"))
      (node (ref "U$1") (pin "12") (pinfunction "P5.4/XIN_12") (pintype "bidirectional"))
      (node (ref "X1") (pin "4") (pinfunction "P$2_4") (pintype "bidirectional"))
    )
    (net (code "59") (name "Net-(U$1-P5.5{slash}XOUT)") (class "Default")
      (node (ref "C31") (pin "1") (pinfunction "1_1") (pintype "passive"))
      (node (ref "U$1") (pin "13") (pinfunction "P5.5/XOUT_13") (pintype "bidirectional"))
      (node (ref "X1") (pin "1") (pinfunction "P$1_1") (pintype "bidirectional"))
    )
    (net (code "60") (name "Net-(U$1-VCORE)") (class "Default")
      (node (ref "C30") (pin "2") (pinfunction "2_2") (pintype "passive"))
      (node (ref "U$1") (pin "17") (pinfunction "VCORE_17") (pintype "bidirectional"))
    )
    (net (code "61") (name "Net-(U$3-EN)") (class "Default")
      (node (ref "R6") (pin "1") (pinfunction "1_1") (pintype "passive"))
      (node (ref "U$3") (pin "4") (pinfunction "EN_4") (pintype "bidirectional"))
    )
    (net (code "62") (name "Net-(U$3-FB)") (class "Default")
      (node (ref "R1") (pin "1") (pinfunction "1_1") (pintype "passive"))
      (node (ref "R2") (pin "2") (pinfunction "2_2") (pintype "passive"))
      (node (ref "U$3") (pin "2") (pinfunction "FB_2") (pintype "bidirectional"))
    )
    (net (code "63") (name "Net-(U$3-ISET1)") (class "Default")
      (node (ref "R5") (pin "1") (pinfunction "1_1") (pintype "passive"))
      (node (ref "U$3") (pin "12") (pinfunction "ISET1_12") (pintype "bidirectional"))
    )
    (net (code "64") (name "Net-(U$3-ISET2)") (class "Default")
      (node (ref "D9") (pin "C") (pinfunction "C_C") (pintype "passive"))
      (node (ref "U$3") (pin "13") (pinfunction "ISET2_13") (pintype "bidirectional"))
    )
    (net (code "65") (name "Net-(U$3-STAT1)") (class "Default")
      (node (ref "R4") (pin "1") (pinfunction "1_1") (pintype "passive"))
      (node (ref "U$3") (pin "7") (pinfunction "STAT1_7") (pintype "bidirectional"))
    )
    (net (code "66") (name "Net-(U$3-STAT2)") (class "Default")
      (node (ref "R3") (pin "1") (pinfunction "1_1") (pintype "passive"))
      (node (ref "U$3") (pin "8") (pinfunction "STAT2_8") (pintype "bidirectional"))
    )
    (net (code "67") (name "Net-(U$8-C11M)") (class "Default")
      (node (ref "C13") (pin "1") (pinfunction "1_1") (pintype "passive"))
      (node (ref "U$8") (pin "28") (pinfunction "C11M_28") (pintype "bidirectional"))
    )
    (net (code "68") (name "Net-(U$8-C11P)") (class "Default")
      (node (ref "C13") (pin "2") (pinfunction "2_2") (pintype "passive"))
      (node (ref "U$8") (pin "29") (pinfunction "C11P_29") (pintype "bidirectional"))
    )
    (net (code "69") (name "Net-(U$8-C12M)") (class "Default")
      (node (ref "C12") (pin "1") (pinfunction "1_1") (pintype "passive"))
      (node (ref "U$8") (pin "26") (pinfunction "C12M_26") (pintype "bidirectional"))
    )
    (net (code "70") (name "Net-(U$8-C12P)") (class "Default")
      (node (ref "C12") (pin "2") (pinfunction "2_2") (pintype "passive"))
      (node (ref "U$8") (pin "27") (pinfunction "C12P_27") (pintype "bidirectional"))
    )
    (net (code "71") (name "Net-(U$8-C13M)") (class "Default")
      (node (ref "C11") (pin "1") (pinfunction "1_1") (pintype "passive"))
      (node (ref "U$8") (pin "24") (pinfunction "C13M_24") (pintype "bidirectional"))
    )
    (net (code "72") (name "Net-(U$8-C13P)") (class "Default")
      (node (ref "C11") (pin "2") (pinfunction "2_2") (pintype "passive"))
      (node (ref "U$8") (pin "25") (pinfunction "C13P_25") (pintype "bidirectional"))
    )
    (net (code "73") (name "Net-(U$8-C14M)") (class "Default")
      (node (ref "C10") (pin "1") (pinfunction "1_1") (pintype "passive"))
      (node (ref "U$8") (pin "22") (pinfunction "C14M_22") (pintype "bidirectional"))
    )
    (net (code "74") (name "Net-(U$8-C14P)") (class "Default")
      (node (ref "C10") (pin "2") (pinfunction "2_2") (pintype "passive"))
      (node (ref "U$8") (pin "23") (pinfunction "C14P_23") (pintype "bidirectional"))
    )
    (net (code "75") (name "Net-(U$8-C15M)") (class "Default")
      (node (ref "C9") (pin "1") (pinfunction "1_1") (pintype "passive"))
      (node (ref "U$8") (pin "20") (pinfunction "C15M_20") (pintype "bidirectional"))
    )
    (net (code "76") (name "Net-(U$8-C15P)") (class "Default")
      (node (ref "C9") (pin "2") (pinfunction "2_2") (pintype "passive"))
      (node (ref "U$8") (pin "21") (pinfunction "C15P_21") (pintype "bidirectional"))
    )
    (net (code "77") (name "Net-(U$8-C16M)") (class "Default")
      (node (ref "C8") (pin "2") (pinfunction "2_2") (pintype "passive"))
      (node (ref "U$8") (pin "18") (pinfunction "C16M_18") (pintype "bidirectional"))
    )
    (net (code "78") (name "Net-(U$8-C16P)") (class "Default")
      (node (ref "C8") (pin "1") (pinfunction "1_1") (pintype "passive"))
      (node (ref "U$8") (pin "19") (pinfunction "C16P_19") (pintype "bidirectional"))
    )
    (net (code "79") (name "Net-(U$8-C21M)") (class "Default")
      (node (ref "C7") (pin "2") (pinfunction "2_2") (pintype "passive"))
      (node (ref "U$8") (pin "16") (pinfunction "C21M_16") (pintype "bidirectional"))
    )
    (net (code "80") (name "Net-(U$8-C21P)") (class "Default")
      (node (ref "C7") (pin "1") (pinfunction "1_1") (pintype "passive"))
      (node (ref "U$8") (pin "17") (pinfunction "C21P_17") (pintype "bidirectional"))
    )
    (net (code "81") (name "Net-(U$8-C31M)") (class "Default")
      (node (ref "C6") (pin "2") (pinfunction "2_2") (pintype "passive"))
      (node (ref "U$8") (pin "14") (pinfunction "C31M_14") (pintype "bidirectional"))
    )
    (net (code "82") (name "Net-(U$8-C31P)") (class "Default")
      (node (ref "C6") (pin "1") (pinfunction "1_1") (pintype "passive"))
      (node (ref "U$8") (pin "15") (pinfunction "C31P_15") (pintype "bidirectional"))
    )
    (net (code "83") (name "Net-(U$8-C41M)") (class "Default")
      (node (ref "C5") (pin "1") (pinfunction "1_1") (pintype "passive"))
      (node (ref "U$8") (pin "13") (pinfunction "C41M_13") (pintype "bidirectional"))
    )
    (net (code "84") (name "Net-(U$8-C41P)") (class "Default")
      (node (ref "C5") (pin "2") (pinfunction "2_2") (pintype "passive"))
      (node (ref "U$8") (pin "12") (pinfunction "C41P_12") (pintype "bidirectional"))
    )
    (net (code "85") (name "Net-(U$8-C42M)") (class "Default")
      (node (ref "C4") (pin "1") (pinfunction "1_1") (pintype "passive"))
      (node (ref "U$8") (pin "11") (pinfunction "C42M_11") (pintype "bidirectional"))
    )
    (net (code "86") (name "Net-(U$8-C42P)") (class "Default")
      (node (ref "C4") (pin "2") (pinfunction "2_2") (pintype "passive"))
      (node (ref "U$8") (pin "10") (pinfunction "C42P_10") (pintype "bidirectional"))
    )
    (net (code "87") (name "Net-(U$8-VCL)") (class "Default")
      (node (ref "C3") (pin "2") (pinfunction "2_2") (pintype "passive"))
      (node (ref "U$8") (pin "9") (pinfunction "VCL_9") (pintype "bidirectional"))
    )
    (net (code "88") (name "Net-(U$12-P$1)") (class "Default")
      (node (ref "R10") (pin "1") (pinfunction "1_1") (pintype "passive"))
      (node (ref "U$12") (pin "1") (pinfunction "P$1_1") (pintype "bidirectional"))
    )
    (net (code "89") (name "unconnected-(U$1-P1.0{slash}TA0CLK{slash}ACLK-Pad18)") (class "Default")
      (node (ref "U$1") (pin "18") (pinfunction "P1.0/TA0CLK/ACLK_18") (pintype "bidirectional"))
    )
    (net (code "90") (name "unconnected-(U$1-P1.2{slash}TA0.1-Pad20)") (class "Default")
      (node (ref "U$1") (pin "20") (pinfunction "P1.2/TA0.1_20") (pintype "bidirectional"))
    )
    (net (code "91") (name "unconnected-(U$1-P1.5{slash}TA0.4-Pad23)") (class "Default")
      (node (ref "U$1") (pin "23") (pinfunction "P1.5/TA0.4_23") (pintype "bidirectional"))
    )
    (net (code "92") (name "unconnected-(U$1-P1.6{slash}TA1CLK{slash}CNOUT-Pad24)") (class "Default")
      (node (ref "U$1") (pin "24") (pinfunction "P1.6/TA1CLK/CNOUT_24") (pintype "bidirectional"))
    )
    (net (code "93") (name "unconnected-(U$1-P1.7{slash}TA1.0-Pad25)") (class "Default")
      (node (ref "U$1") (pin "25") (pinfunction "P1.7/TA1.0_25") (pintype "bidirectional"))
    )
    (net (code "94") (name "unconnected-(U$1-P2.4{slash}TA2.1-Pad30)") (class "Default")
      (node (ref "U$1") (pin "30") (pinfunction "P2.4/TA2.1_30") (pintype "bidirectional"))
    )
    (net (code "95") (name "unconnected-(U$1-P2.5{slash}TA2.2-Pad31)") (class "Default")
      (node (ref "U$1") (pin "31") (pinfunction "P2.5/TA2.2_31") (pintype "bidirectional"))
    )
    (net (code "96") (name "unconnected-(U$1-P2.6{slash}RTCOLK{slash}DMAE0-Pad32)") (class "Default")
      (node (ref "U$1") (pin "32") (pinfunction "P2.6/RTCOLK/DMAE0_32") (pintype "bidirectional"))
    )
    (net (code "97") (name "unconnected-(U$1-P2.7{slash}UCB0STE{slash}UCA0CLK-Pad33)") (class "Default")
      (node (ref "U$1") (pin "33") (pinfunction "P2.7/UCB0STE/UCA0CLK_33") (pintype "bidirectional"))
    )
    (net (code "98") (name "unconnected-(U$1-P3.4{slash}UCA0RXD{slash}UCA0SOMI-Pad38)") (class "Default")
      (node (ref "U$1") (pin "38") (pinfunction "P3.4/UCA0RXD/UCA0SOMI_38") (pintype "bidirectional"))
    )
    (net (code "99") (name "unconnected-(U$1-P4.0{slash}PM_UCB1STE{slash}PM_UCA1CLK-Pad41)") (class "Default")
      (node (ref "U$1") (pin "41") (pinfunction "P4.0/PM_UCB1STE/PM_UCA1CLK_41") (pintype "bidirectional"))
    )
    (net (code "100") (name "unconnected-(U$1-P5.0{slash}A8{slash}VREF+-Pad9)") (class "Default")
      (node (ref "U$1") (pin "9") (pinfunction "P5.0/A8/VREF+_9") (pintype "bidirectional"))
    )
    (net (code "101") (name "unconnected-(U$1-P5.1{slash}A9{slash}VREF--Pad10)") (class "Default")
      (node (ref "U$1") (pin "10") (pinfunction "P5.1/A9/VREF-_10") (pintype "bidirectional"))
    )
    (net (code "102") (name "unconnected-(U$1-P5.2{slash}XT2IN-Pad57)") (class "Default")
      (node (ref "U$1") (pin "57") (pinfunction "P5.2/XT2IN_57") (pintype "bidirectional"))
    )
    (net (code "103") (name "unconnected-(U$1-P5.3{slash}XT2OUT-Pad58)") (class "Default")
      (node (ref "U$1") (pin "58") (pinfunction "P5.3/XT2OUT_58") (pintype "bidirectional"))
    )
    (net (code "104") (name "unconnected-(U$1-PJ.0{slash}TDO-Pad60)") (class "Default")
      (node (ref "U$1") (pin "60") (pinfunction "PJ.0/TDO_60") (pintype "bidirectional"))
    )
    (net (code "105") (name "unconnected-(U$1-PJ.1{slash}TDI{slash}TCLK-Pad61)") (class "Default")
      (node (ref "U$1") (pin "61") (pinfunction "PJ.1/TDI/TCLK_61") (pintype "bidirectional"))
    )
    (net (code "106") (name "unconnected-(U$1-PJ.2{slash}TMS-Pad62)") (class "Default")
      (node (ref "U$1") (pin "62") (pinfunction "PJ.2/TMS_62") (pintype "bidirectional"))
    )
    (net (code "107") (name "unconnected-(U$1-PJ.3{slash}TCK-Pad63)") (class "Default")
      (node (ref "U$1") (pin "63") (pinfunction "PJ.3/TCK_63") (pintype "bidirectional"))
    )
    (net (code "108") (name "unconnected-(U$1-PU.0{slash}DP-Pad50)") (class "Default")
      (node (ref "U$1") (pin "50") (pinfunction "PU.0/DP_50") (pintype "bidirectional"))
    )
    (net (code "109") (name "unconnected-(U$1-PU.1{slash}DM-Pad52)") (class "Default")
      (node (ref "U$1") (pin "52") (pinfunction "PU.1/DM_52") (pintype "bidirectional"))
    )
    (net (code "110") (name "unconnected-(U$1-PUR-Pad51)") (class "Default")
      (node (ref "U$1") (pin "51") (pinfunction "PUR_51") (pintype "bidirectional"))
    )
    (net (code "111") (name "unconnected-(U$1-V18-Pad55)") (class "Default")
      (node (ref "U$1") (pin "55") (pinfunction "V18_55") (pintype "bidirectional"))
    )
    (net (code "112") (name "unconnected-(U$1-VBUS-Pad53)") (class "Default")
      (node (ref "U$1") (pin "53") (pinfunction "VBUS_53") (pintype "bidirectional"))
    )
    (net (code "113") (name "unconnected-(U$1-VUSB-Pad54)") (class "Default")
      (node (ref "U$1") (pin "54") (pinfunction "VUSB_54") (pintype "bidirectional"))
    )
    (net (code "114") (name "unconnected-(U$2-AIO0-Pad30)") (class "Default")
      (node (ref "U$2") (pin "30") (pinfunction "AIO0_30") (pintype "bidirectional"))
    )
    (net (code "115") (name "unconnected-(U$2-AIO1-Pad35)") (class "Default")
      (node (ref "U$2") (pin "35") (pinfunction "AIO1_35") (pintype "bidirectional"))
    )
    (net (code "116") (name "unconnected-(U$2-PCM_CLK-Pad7)") (class "Default")
      (node (ref "U$2") (pin "7") (pinfunction "PCM_CLK_7") (pintype "bidirectional"))
    )
    (net (code "117") (name "unconnected-(U$2-PCM_IN-Pad9)") (class "Default")
      (node (ref "U$2") (pin "9") (pinfunction "PCM_IN_9") (pintype "bidirectional"))
    )
    (net (code "118") (name "unconnected-(U$2-PCM_OUT-Pad10)") (class "Default")
      (node (ref "U$2") (pin "10") (pinfunction "PCM_OUT_10") (pintype "bidirectional"))
    )
    (net (code "119") (name "unconnected-(U$2-PCM_SYNC-Pad8)") (class "Default")
      (node (ref "U$2") (pin "8") (pinfunction "PCM_SYNC_8") (pintype "bidirectional"))
    )
    (net (code "120") (name "unconnected-(U$2-PIO3-Pad20)") (class "Default")
      (node (ref "U$2") (pin "20") (pinfunction "PIO3_20") (pintype "bidirectional"))
    )
    (net (code "121") (name "unconnected-(U$2-PIO4-Pad22)") (class "Default")
      (node (ref "U$2") (pin "22") (pinfunction "PIO4_22") (pintype "bidirectional"))
    )
    (net (code "122") (name "unconnected-(U$2-PIO5-Pad21)") (class "Default")
      (node (ref "U$2") (pin "21") (pinfunction "PIO5_21") (pintype "bidirectional"))
    )
    (net (code "123") (name "unconnected-(U$2-PIO6-Pad3)") (class "Default")
      (node (ref "U$2") (pin "3") (pinfunction "PIO6_3") (pintype "bidirectional"))
    )
    (net (code "124") (name "unconnected-(U$2-PIO8-Pad31)") (class "Default")
      (node (ref "U$2") (pin "31") (pinfunction "PIO8_31") (pintype "bidirectional"))
    )
    (net (code "125") (name "unconnected-(U$2-PIO9-Pad32)") (class "Default")
      (node (ref "U$2") (pin "32") (pinfunction "PIO9_32") (pintype "bidirectional"))
    )
    (net (code "126") (name "unconnected-(U$2-PIO10-Pad33)") (class "Default")
      (node (ref "U$2") (pin "33") (pinfunction "PIO10_33") (pintype "bidirectional"))
    )
    (net (code "127") (name "unconnected-(U$2-PIO11-Pad34)") (class "Default")
      (node (ref "U$2") (pin "34") (pinfunction "PIO11_34") (pintype "bidirectional"))
    )
    (net (code "128") (name "unconnected-(U$2-RST-Pad5)") (class "Default")
      (node (ref "U$2") (pin "5") (pinfunction "RST_5") (pintype "bidirectional"))
    )
    (net (code "129") (name "unconnected-(U$2-SPI_CLK-Pad6)") (class "Default")
      (node (ref "U$2") (pin "6") (pinfunction "SPI_CLK_6") (pintype "bidirectional"))
    )
    (net (code "130") (name "unconnected-(U$2-SPI_CSB-Pad23)") (class "Default")
      (node (ref "U$2") (pin "23") (pinfunction "SPI_CSB_23") (pintype "bidirectional"))
    )
    (net (code "131") (name "unconnected-(U$2-SPI_MISO-Pad24)") (class "Default")
      (node (ref "U$2") (pin "24") (pinfunction "SPI_MISO_24") (pintype "bidirectional"))
    )
    (net (code "132") (name "unconnected-(U$2-SPI_MOSI-Pad2)") (class "Default")
      (node (ref "U$2") (pin "2") (pinfunction "SPI_MOSI_2") (pintype "bidirectional"))
    )
    (net (code "133") (name "unconnected-(U$2-UART_RTS-Pad15)") (class "Default")
      (node (ref "U$2") (pin "15") (pinfunction "UART_RTS_15") (pintype "bidirectional"))
    )
    (net (code "134") (name "unconnected-(U$2-USART_CTS-Pad16)") (class "Default")
      (node (ref "U$2") (pin "16") (pinfunction "USART_CTS_16") (pintype "bidirectional"))
    )
    (net (code "135") (name "unconnected-(U$2-USB_D+-Pad17)") (class "Default")
      (node (ref "U$2") (pin "17") (pinfunction "USB_D+_17") (pintype "bidirectional"))
    )
    (net (code "136") (name "unconnected-(U$2-USB_D--Pad18)") (class "Default")
      (node (ref "U$2") (pin "18") (pinfunction "USB_D-_18") (pintype "bidirectional"))
    )
    (net (code "137") (name "unconnected-(U$3-AC-Pad5)") (class "Default")
      (node (ref "U$3") (pin "5") (pinfunction "AC_5") (pintype "bidirectional"))
    )
    (net (code "138") (name "unconnected-(U$3-PG-Pad14)") (class "Default")
      (node (ref "U$3") (pin "14") (pinfunction "PG_14") (pintype "bidirectional"))
    )
    (net (code "139") (name "unconnected-(U$8-ADC_IN-Pad8)") (class "Default")
      (node (ref "U$8") (pin "8") (pinfunction "ADC_IN_8") (pintype "bidirectional"))
    )
  )
)
